# controller-main_2.net
KiCad netlist of a schematic drawn in EAGLE
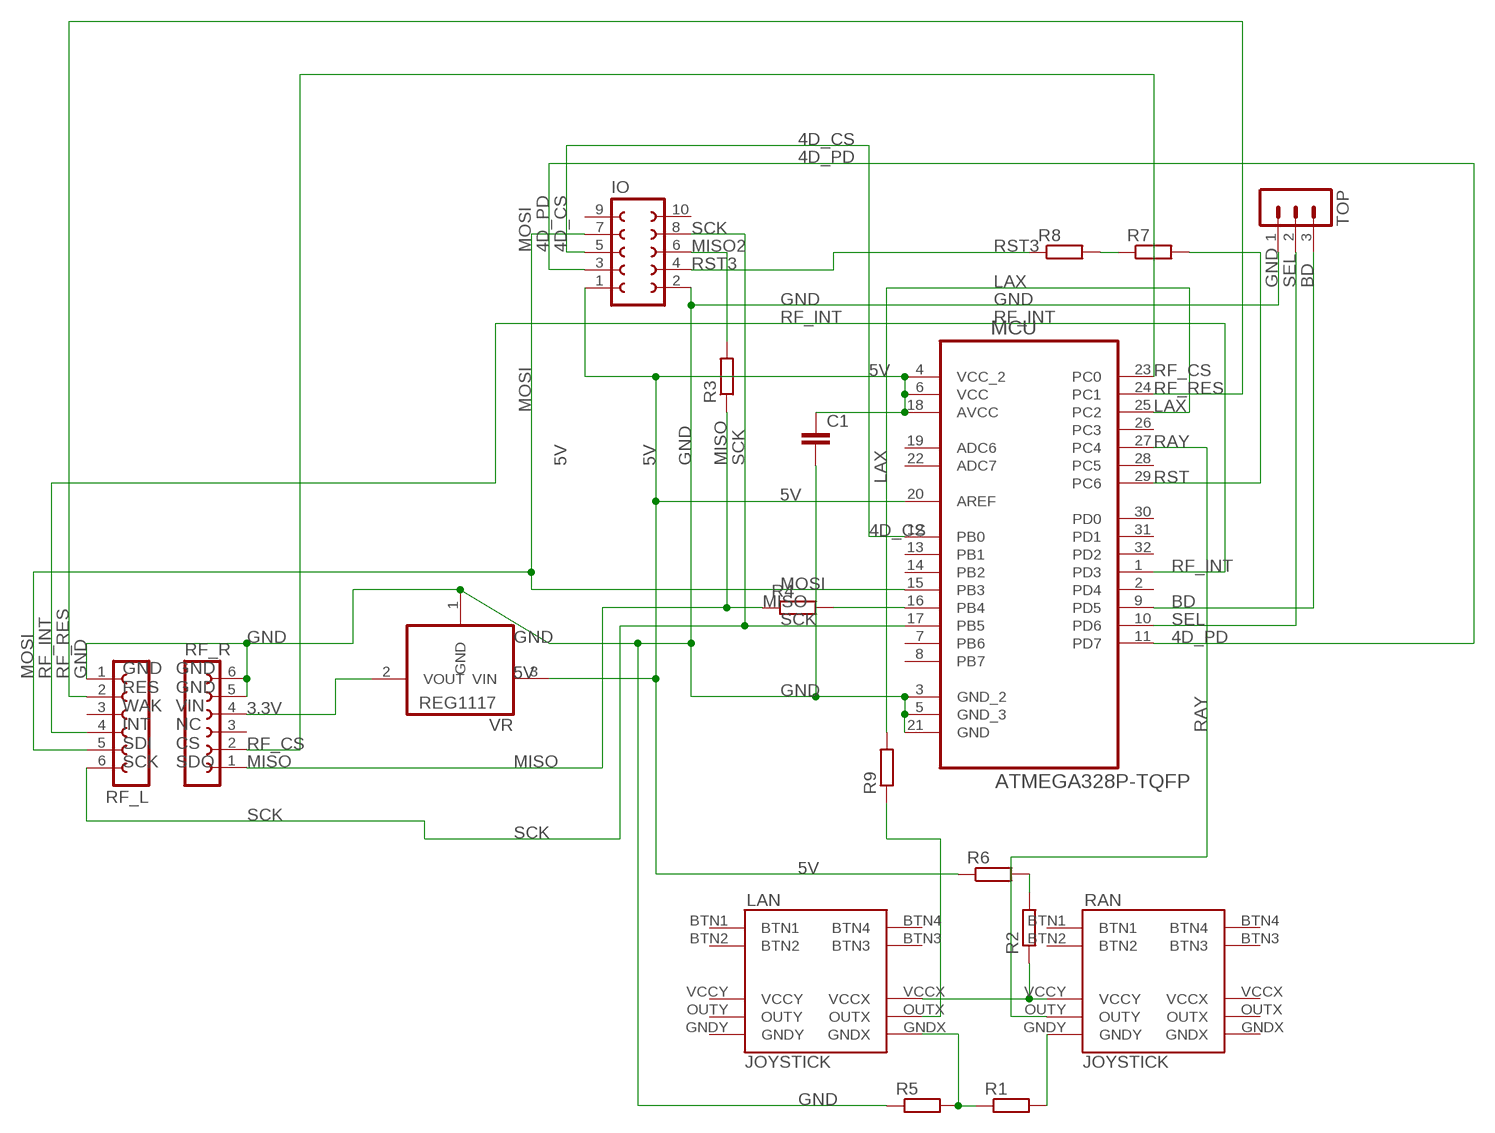
[diagram p0: schematic, sheet 1]

(export (version "E")
  (design (tool "Eeschema 10.0.6"))
  (components
    (comp (ref "C1")
      (value "C-EUC1206")
      (footprint "eagle-import:C1206")
      (libsource (lib "eagle-import") (part "C-EUC1206"))
    )
    (comp (ref "IO")
      (value "FE05-2W")
      (footprint "eagle-import:FE05-2W")
      (libsource (lib "eagle-import") (part "FE05-2W"))
    )
    (comp (ref "LAN")
      (value "JOYSTICK")
      (footprint "eagle-import:JOYSTICK")
      (libsource (lib "eagle-import") (part "JOYSTICKJOYSTICKWBTN"))
    )
    (comp (ref "MCU")
      (value "ATMEGA328P-TQFP")
      (footprint "eagle-import:QFP80P900X900X120-32N")
      (fields (field (name "MPN") "ATMEGA328P-AU"))
      (libsource (lib "eagle-import") (part "ATMEGA328P-AU"))
    )
    (comp (ref "R1")
      (value "R-EU_M1206")
      (footprint "eagle-import:M1206")
      (libsource (lib "eagle-import") (part "R-EU_M1206"))
    )
    (comp (ref "R2")
      (value "R-EU_M1206")
      (footprint "eagle-import:M1206")
      (libsource (lib "eagle-import") (part "R-EU_M1206"))
    )
    (comp (ref "R3")
      (value "R-EU_M1206")
      (footprint "eagle-import:M1206")
      (libsource (lib "eagle-import") (part "R-EU_M1206"))
    )
    (comp (ref "R4")
      (value "R-EU_M1206")
      (footprint "eagle-import:M1206")
      (libsource (lib "eagle-import") (part "R-EU_M1206"))
    )
    (comp (ref "R5")
      (value "R-EU_M1206")
      (footprint "eagle-import:M1206")
      (libsource (lib "eagle-import") (part "R-EU_M1206"))
    )
    (comp (ref "R6")
      (value "R-EU_M1206")
      (footprint "eagle-import:M1206")
      (libsource (lib "eagle-import") (part "R-EU_M1206"))
    )
    (comp (ref "R7")
      (value "R-EU_M1206")
      (footprint "eagle-import:M1206")
      (libsource (lib "eagle-import") (part "R-EU_M1206"))
    )
    (comp (ref "R8")
      (value "R-EU_M1206")
      (footprint "eagle-import:M1206")
      (libsource (lib "eagle-import") (part "R-EU_M1206"))
    )
    (comp (ref "R9")
      (value "R-EU_M1206")
      (footprint "eagle-import:M1206")
      (libsource (lib "eagle-import") (part "R-EU_M1206"))
    )
    (comp (ref "RAN")
      (value "JOYSTICK")
      (footprint "eagle-import:JOYSTICK")
      (libsource (lib "eagle-import") (part "JOYSTICKJOYSTICKWBTN"))
    )
    (comp (ref "RF_L")
      (value "FE06-1")
      (footprint "eagle-import:FE06")
      (libsource (lib "eagle-import") (part "FE06-1"))
    )
    (comp (ref "RF_R")
      (value "FE06-1")
      (footprint "eagle-import:FE06")
      (libsource (lib "eagle-import") (part "FE06-1"))
    )
    (comp (ref "TOP")
      (value "MA03-1")
      (footprint "eagle-import:MA03-1")
      (libsource (lib "eagle-import") (part "MA03-1"))
    )
    (comp (ref "VR")
      (value "REG1117")
      (footprint "eagle-import:SOT223")
      (libsource (lib "eagle-import") (part "REG1117"))
    )
  )
  (nets
    (net (code "1") (name "/3.3V") (class "Default")
      (node (ref "RF_R") (pin "4") (pinfunction "4_4") (pintype "passive"))
      (node (ref "VR") (pin "2") (pinfunction "VOUT_2") (pintype "output"))
    )
    (net (code "2") (name "/4D_CS") (class "Default")
      (node (ref "IO") (pin "5") (pinfunction "5_5") (pintype "passive"))
      (node (ref "MCU") (pin "12") (pinfunction "PB0_12") (pintype "bidirectional"))
    )
    (net (code "3") (name "/4D_PD") (class "Default")
      (node (ref "IO") (pin "3") (pinfunction "3_3") (pintype "passive"))
      (node (ref "MCU") (pin "11") (pinfunction "PD7_11") (pintype "bidirectional"))
    )
    (net (code "4") (name "/5V") (class "Default")
      (node (ref "C1") (pin "1") (pinfunction "1_1") (pintype "passive"))
      (node (ref "IO") (pin "1") (pinfunction "1_1") (pintype "passive"))
      (node (ref "MCU") (pin "18") (pinfunction "AVCC_18") (pintype "power_in"))
      (node (ref "MCU") (pin "20") (pinfunction "AREF_20") (pintype "input"))
      (node (ref "MCU") (pin "4") (pinfunction "VCC_2_4") (pintype "power_in"))
      (node (ref "MCU") (pin "6") (pinfunction "VCC_6") (pintype "power_in"))
      (node (ref "R6") (pin "1") (pinfunction "1_1") (pintype "passive"))
      (node (ref "VR") (pin "3") (pinfunction "VIN_3") (pintype "input"))
    )
    (net (code "5") (name "/BD") (class "Default")
      (node (ref "MCU") (pin "9") (pinfunction "PD5_9") (pintype "bidirectional"))
      (node (ref "TOP") (pin "3") (pinfunction "3_3") (pintype "passive"))
    )
    (net (code "6") (name "/GND") (class "Default")
      (node (ref "C1") (pin "2") (pinfunction "2_2") (pintype "passive"))
      (node (ref "IO") (pin "2") (pinfunction "2_2") (pintype "passive"))
      (node (ref "MCU") (pin "21") (pinfunction "GND_21") (pintype "passive"))
      (node (ref "MCU") (pin "3") (pinfunction "GND_2_3") (pintype "passive"))
      (node (ref "MCU") (pin "5") (pinfunction "GND_3_5") (pintype "passive"))
      (node (ref "R5") (pin "1") (pinfunction "1_1") (pintype "passive"))
      (node (ref "RF_L") (pin "1") (pinfunction "1_1") (pintype "passive"))
      (node (ref "RF_R") (pin "5") (pinfunction "5_5") (pintype "passive"))
      (node (ref "RF_R") (pin "6") (pinfunction "6_6") (pintype "passive"))
      (node (ref "TOP") (pin "1") (pinfunction "1_1") (pintype "passive"))
      (node (ref "VR") (pin "1") (pinfunction "GND_1") (pintype "power_in"))
    )
    (net (code "7") (name "/LAX") (class "Default")
      (node (ref "MCU") (pin "25") (pinfunction "PC2_25") (pintype "bidirectional"))
      (node (ref "R9") (pin "2") (pinfunction "2_2") (pintype "passive"))
    )
    (net (code "8") (name "/MISO") (class "Default")
      (node (ref "R3") (pin "1") (pinfunction "1_1") (pintype "passive"))
      (node (ref "R4") (pin "1") (pinfunction "1_1") (pintype "passive"))
      (node (ref "RF_R") (pin "1") (pinfunction "1_1") (pintype "passive"))
    )
    (net (code "9") (name "/MISO2") (class "Default")
      (node (ref "IO") (pin "6") (pinfunction "6_6") (pintype "passive"))
      (node (ref "R3") (pin "2") (pinfunction "2_2") (pintype "passive"))
    )
    (net (code "10") (name "/MOSI") (class "Default")
      (node (ref "IO") (pin "7") (pinfunction "7_7") (pintype "passive"))
      (node (ref "MCU") (pin "15") (pinfunction "PB3_15") (pintype "bidirectional"))
      (node (ref "RF_L") (pin "5") (pinfunction "5_5") (pintype "passive"))
    )
    (net (code "11") (name "/RAY") (class "Default")
      (node (ref "MCU") (pin "27") (pinfunction "PC4_27") (pintype "bidirectional"))
      (node (ref "RAN") (pin "OUTY") (pinfunction "OUTY_OUTY") (pintype "bidirectional"))
    )
    (net (code "12") (name "/RF_CS") (class "Default")
      (node (ref "MCU") (pin "23") (pinfunction "PC0_23") (pintype "bidirectional"))
      (node (ref "RF_R") (pin "2") (pinfunction "2_2") (pintype "passive"))
    )
    (net (code "13") (name "/RF_INT") (class "Default")
      (node (ref "MCU") (pin "1") (pinfunction "PD3_1") (pintype "bidirectional"))
      (node (ref "RF_L") (pin "4") (pinfunction "4_4") (pintype "passive"))
    )
    (net (code "14") (name "/RF_RES") (class "Default")
      (node (ref "MCU") (pin "24") (pinfunction "PC1_24") (pintype "bidirectional"))
      (node (ref "RF_L") (pin "2") (pinfunction "2_2") (pintype "passive"))
    )
    (net (code "15") (name "/RST") (class "Default")
      (node (ref "MCU") (pin "29") (pinfunction "PC6_29") (pintype "bidirectional"))
      (node (ref "R7") (pin "2") (pinfunction "2_2") (pintype "passive"))
    )
    (net (code "16") (name "/RST3") (class "Default")
      (node (ref "IO") (pin "4") (pinfunction "4_4") (pintype "passive"))
      (node (ref "R8") (pin "1") (pinfunction "1_1") (pintype "passive"))
    )
    (net (code "17") (name "/SCK") (class "Default")
      (node (ref "IO") (pin "8") (pinfunction "8_8") (pintype "passive"))
      (node (ref "MCU") (pin "17") (pinfunction "PB5_17") (pintype "bidirectional"))
      (node (ref "RF_L") (pin "6") (pinfunction "6_6") (pintype "passive"))
    )
    (net (code "18") (name "/SEL") (class "Default")
      (node (ref "MCU") (pin "10") (pinfunction "PD6_10") (pintype "bidirectional"))
      (node (ref "TOP") (pin "2") (pinfunction "2_2") (pintype "passive"))
    )
    (net (code "19") (name "Net-(LAN-PadGNDX)") (class "Default")
      (node (ref "LAN") (pin "GNDX") (pinfunction "GNDX_GNDX") (pintype "bidirectional"))
      (node (ref "R1") (pin "1") (pinfunction "1_1") (pintype "passive"))
      (node (ref "R5") (pin "2") (pinfunction "2_2") (pintype "passive"))
    )
    (net (code "20") (name "Net-(LAN-PadOUTX)") (class "Default")
      (node (ref "LAN") (pin "OUTX") (pinfunction "OUTX_OUTX") (pintype "bidirectional"))
      (node (ref "R9") (pin "1") (pinfunction "1_1") (pintype "passive"))
    )
    (net (code "21") (name "Net-(LAN-PadVCCX)") (class "Default")
      (node (ref "LAN") (pin "VCCX") (pinfunction "VCCX_VCCX") (pintype "bidirectional"))
      (node (ref "R2") (pin "1") (pinfunction "1_1") (pintype "passive"))
      (node (ref "RAN") (pin "VCCY") (pinfunction "VCCY_VCCY") (pintype "bidirectional"))
    )
    (net (code "22") (name "Net-(MCU-PB4)") (class "Default")
      (node (ref "MCU") (pin "16") (pinfunction "PB4_16") (pintype "bidirectional"))
      (node (ref "R4") (pin "2") (pinfunction "2_2") (pintype "passive"))
    )
    (net (code "23") (name "Net-(R1-Pad2)") (class "Default")
      (node (ref "R1") (pin "2") (pinfunction "2_2") (pintype "passive"))
      (node (ref "RAN") (pin "GNDY") (pinfunction "GNDY_GNDY") (pintype "bidirectional"))
    )
    (net (code "24") (name "Net-(R2-Pad2)") (class "Default")
      (node (ref "R2") (pin "2") (pinfunction "2_2") (pintype "passive"))
      (node (ref "R6") (pin "2") (pinfunction "2_2") (pintype "passive"))
    )
    (net (code "25") (name "Net-(R7-Pad1)") (class "Default")
      (node (ref "R7") (pin "1") (pinfunction "1_1") (pintype "passive"))
      (node (ref "R8") (pin "2") (pinfunction "2_2") (pintype "passive"))
    )
    (net (code "26") (name "unconnected-(IO-Pad9)") (class "Default")
      (node (ref "IO") (pin "9") (pinfunction "9_9") (pintype "passive"))
    )
    (net (code "27") (name "unconnected-(IO-Pad10)") (class "Default")
      (node (ref "IO") (pin "10") (pinfunction "10_10") (pintype "passive"))
    )
    (net (code "28") (name "unconnected-(LAN-PadBTN1)") (class "Default")
      (node (ref "LAN") (pin "BTN1") (pinfunction "BTN1_BTN1") (pintype "bidirectional"))
    )
    (net (code "29") (name "unconnected-(LAN-PadBTN2)") (class "Default")
      (node (ref "LAN") (pin "BTN2") (pinfunction "BTN2_BTN2") (pintype "bidirectional"))
    )
    (net (code "30") (name "unconnected-(LAN-PadBTN3)") (class "Default")
      (node (ref "LAN") (pin "BTN3") (pinfunction "BTN3_BTN3") (pintype "bidirectional"))
    )
    (net (code "31") (name "unconnected-(LAN-PadBTN4)") (class "Default")
      (node (ref "LAN") (pin "BTN4") (pinfunction "BTN4_BTN4") (pintype "bidirectional"))
    )
    (net (code "32") (name "unconnected-(LAN-PadGNDY)") (class "Default")
      (node (ref "LAN") (pin "GNDY") (pinfunction "GNDY_GNDY") (pintype "bidirectional"))
    )
    (net (code "33") (name "unconnected-(LAN-PadOUTY)") (class "Default")
      (node (ref "LAN") (pin "OUTY") (pinfunction "OUTY_OUTY") (pintype "bidirectional"))
    )
    (net (code "34") (name "unconnected-(LAN-PadVCCY)") (class "Default")
      (node (ref "LAN") (pin "VCCY") (pinfunction "VCCY_VCCY") (pintype "bidirectional"))
    )
    (net (code "35") (name "unconnected-(MCU-ADC6-Pad19)") (class "Default")
      (node (ref "MCU") (pin "19") (pinfunction "ADC6_19") (pintype "input"))
    )
    (net (code "36") (name "unconnected-(MCU-ADC7-Pad22)") (class "Default")
      (node (ref "MCU") (pin "22") (pinfunction "ADC7_22") (pintype "input"))
    )
    (net (code "37") (name "unconnected-(MCU-PB1-Pad13)") (class "Default")
      (node (ref "MCU") (pin "13") (pinfunction "PB1_13") (pintype "bidirectional"))
    )
    (net (code "38") (name "unconnected-(MCU-PB2-Pad14)") (class "Default")
      (node (ref "MCU") (pin "14") (pinfunction "PB2_14") (pintype "bidirectional"))
    )
    (net (code "39") (name "unconnected-(MCU-PB6-Pad7)") (class "Default")
      (node (ref "MCU") (pin "7") (pinfunction "PB6_7") (pintype "bidirectional"))
    )
    (net (code "40") (name "unconnected-(MCU-PB7-Pad8)") (class "Default")
      (node (ref "MCU") (pin "8") (pinfunction "PB7_8") (pintype "bidirectional"))
    )
    (net (code "41") (name "unconnected-(MCU-PC3-Pad26)") (class "Default")
      (node (ref "MCU") (pin "26") (pinfunction "PC3_26") (pintype "bidirectional"))
    )
    (net (code "42") (name "unconnected-(MCU-PC5-Pad28)") (class "Default")
      (node (ref "MCU") (pin "28") (pinfunction "PC5_28") (pintype "bidirectional"))
    )
    (net (code "43") (name "unconnected-(MCU-PD0-Pad30)") (class "Default")
      (node (ref "MCU") (pin "30") (pinfunction "PD0_30") (pintype "bidirectional"))
    )
    (net (code "44") (name "unconnected-(MCU-PD1-Pad31)") (class "Default")
      (node (ref "MCU") (pin "31") (pinfunction "PD1_31") (pintype "bidirectional"))
    )
    (net (code "45") (name "unconnected-(MCU-PD2-Pad32)") (class "Default")
      (node (ref "MCU") (pin "32") (pinfunction "PD2_32") (pintype "bidirectional"))
    )
    (net (code "46") (name "unconnected-(MCU-PD4-Pad2)") (class "Default")
      (node (ref "MCU") (pin "2") (pinfunction "PD4_2") (pintype "bidirectional"))
    )
    (net (code "47") (name "unconnected-(RAN-PadBTN1)") (class "Default")
      (node (ref "RAN") (pin "BTN1") (pinfunction "BTN1_BTN1") (pintype "bidirectional"))
    )
    (net (code "48") (name "unconnected-(RAN-PadBTN2)") (class "Default")
      (node (ref "RAN") (pin "BTN2") (pinfunction "BTN2_BTN2") (pintype "bidirectional"))
    )
    (net (code "49") (name "unconnected-(RAN-PadBTN3)") (class "Default")
      (node (ref "RAN") (pin "BTN3") (pinfunction "BTN3_BTN3") (pintype "bidirectional"))
    )
    (net (code "50") (name "unconnected-(RAN-PadBTN4)") (class "Default")
      (node (ref "RAN") (pin "BTN4") (pinfunction "BTN4_BTN4") (pintype "bidirectional"))
    )
    (net (code "51") (name "unconnected-(RAN-PadGNDX)") (class "Default")
      (node (ref "RAN") (pin "GNDX") (pinfunction "GNDX_GNDX") (pintype "bidirectional"))
    )
    (net (code "52") (name "unconnected-(RAN-PadOUTX)") (class "Default")
      (node (ref "RAN") (pin "OUTX") (pinfunction "OUTX_OUTX") (pintype "bidirectional"))
    )
    (net (code "53") (name "unconnected-(RAN-PadVCCX)") (class "Default")
      (node (ref "RAN") (pin "VCCX") (pinfunction "VCCX_VCCX") (pintype "bidirectional"))
    )
    (net (code "54") (name "unconnected-(RF_L-Pad3)") (class "Default")
      (node (ref "RF_L") (pin "3") (pinfunction "3_3") (pintype "passive"))
    )
    (net (code "55") (name "unconnected-(RF_R-Pad3)") (class "Default")
      (node (ref "RF_R") (pin "3") (pinfunction "3_3") (pintype "passive"))
    )
  )
)
